# tracker1.net
KiCad netlist of a schematic drawn in EAGLE
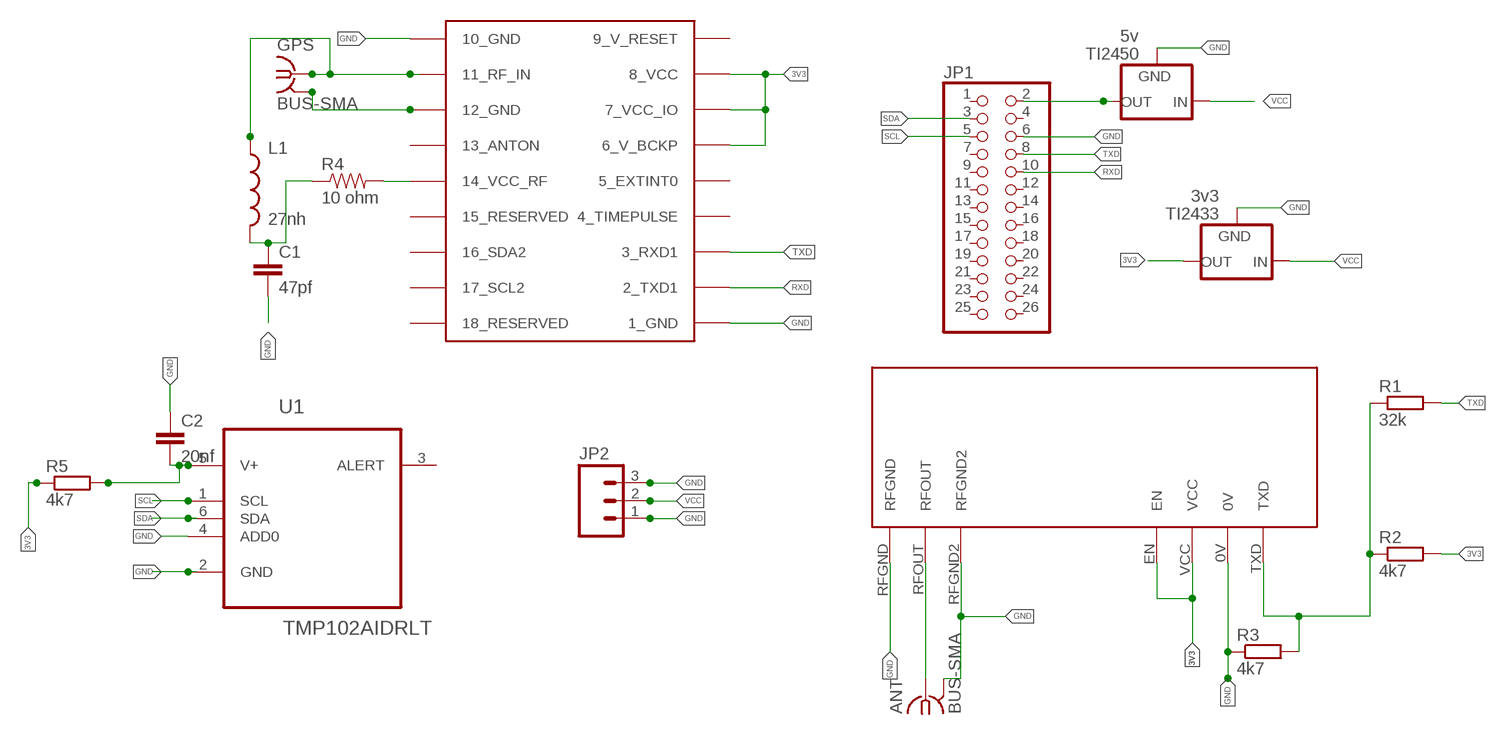
[diagram p0: schematic, sheet 1]

(export (version "E")
  (design (tool "Eeschema 10.0.6"))
  (components
    (comp (ref "ANT")
      (value "BUS-SMA")
      (footprint "eagle-import:BUS-SMA")
      (libsource (lib "eagle-import") (part "BUS-SMA"))
    )
    (comp (ref "C1")
      (value "47pf")
      (footprint "eagle-import:0603-CAP")
      (libsource (lib "eagle-import") (part "CAP0603-CAP"))
    )
    (comp (ref "C2")
      (value "20nf")
      (footprint "eagle-import:C0603")
      (libsource (lib "eagle-import") (part "C-EUC0603"))
    )
    (comp (ref "GPS")
      (value "BUS-SMA")
      (footprint "eagle-import:BUS-SMA")
      (libsource (lib "eagle-import") (part "BUS-SMA"))
    )
    (comp (ref "JP1")
      (value "PINHD-2X13")
      (footprint "eagle-import:2X13")
      (libsource (lib "eagle-import") (part "PINHD-2X13"))
    )
    (comp (ref "JP2")
      (value "M03PTH")
      (footprint "eagle-import:1X03")
      (libsource (lib "eagle-import") (part "M03PTH"))
    )
    (comp (ref "L1")
      (value "27nh")
      (footprint "eagle-import:0603")
      (libsource (lib "eagle-import") (part "INDUCTOR0603"))
    )
    (comp (ref "R1")
      (value "32k")
      (footprint "eagle-import:R0603")
      (libsource (lib "eagle-import") (part "R-EU_R0603"))
    )
    (comp (ref "R2")
      (value "4k7")
      (footprint "eagle-import:R0603")
      (libsource (lib "eagle-import") (part "R-EU_R0603"))
    )
    (comp (ref "R3")
      (value "4k7")
      (footprint "eagle-import:R0603")
      (libsource (lib "eagle-import") (part "R-EU_R0603"))
    )
    (comp (ref "R4")
      (value "10 ohm")
      (footprint "eagle-import:0603-RES")
      (libsource (lib "eagle-import") (part "RESISTOR0603"))
    )
    (comp (ref "R5")
      (value "4k7")
      (footprint "eagle-import:R0603")
      (libsource (lib "eagle-import") (part "R-EU_R0603"))
    )
    (comp (ref "TI2433")
      (value "3v3")
      (footprint "eagle-import:TO-220-ALT")
      (libsource (lib "eagle-import") (part "V_REG_78XX-TO-220"))
    )
    (comp (ref "TI2450")
      (value "5v")
      (footprint "eagle-import:TO-220-ALT")
      (libsource (lib "eagle-import") (part "V_REG_78XX-TO-220"))
    )
    (comp (ref "U$1")
      (value "NTX2")
      (footprint "eagle-import:NTX2")
      (libsource (lib "eagle-import") (part "NTX2"))
    )
    (comp (ref "U$2")
      (value "UBLOX_MAX")
      (footprint "eagle-import:UBLOX_MAX")
      (libsource (lib "eagle-import") (part "UBLOX_MAX"))
    )
    (comp (ref "U1")
      (value "TMP102AIDRLT")
      (footprint "eagle-import:SOT50P160X60-6N")
      (libsource (lib "eagle-import") (part "TMP102AIDRLT"))
    )
  )
  (nets
    (net (code "1") (name "/9_V_RESET") (class "Default")
      (node (ref "U$2") (pin "9_V_RESET") (pinfunction "9_V_RESET_9_V_RESET") (pintype "power_in"))
    )
    (net (code "2") (name "3V3") (class "Default")
      (node (ref "C2") (pin "2") (pinfunction "2_2") (pintype "passive"))
      (node (ref "R2") (pin "2") (pinfunction "2_2") (pintype "passive"))
      (node (ref "R5") (pin "1") (pinfunction "1_1") (pintype "passive"))
      (node (ref "R5") (pin "2") (pinfunction "2_2") (pintype "passive"))
      (node (ref "TI2433") (pin "OUT") (pinfunction "OUT_OUT") (pintype "output"))
      (node (ref "U$1") (pin "EN") (pinfunction "EN_EN") (pintype "bidirectional"))
      (node (ref "U$1") (pin "VCC") (pinfunction "VCC_VCC") (pintype "bidirectional"))
      (node (ref "U$2") (pin "6_V_BCKP") (pinfunction "6_V_BCKP_6_V_BCKP") (pintype "bidirectional"))
      (node (ref "U$2") (pin "7_VCC_IO") (pinfunction "7_VCC_IO_7_VCC_IO") (pintype "power_in"))
      (node (ref "U$2") (pin "8_VCC") (pinfunction "8_VCC_8_VCC") (pintype "power_in"))
      (node (ref "U1") (pin "5") (pinfunction "V+_5") (pintype "power_in"))
    )
    (net (code "3") (name "GND") (class "Default")
      (node (ref "ANT") (pin "2") (pinfunction "GND_2") (pintype "power_in"))
      (node (ref "ANT") (pin "3") (pinfunction "GND_3") (pintype "power_in"))
      (node (ref "ANT") (pin "4") (pinfunction "GND_4") (pintype "power_in"))
      (node (ref "ANT") (pin "5") (pinfunction "GND_5") (pintype "power_in"))
      (node (ref "C1") (pin "2") (pinfunction "2_2") (pintype "passive"))
      (node (ref "C2") (pin "1") (pinfunction "1_1") (pintype "passive"))
      (node (ref "GPS") (pin "2") (pinfunction "GND_2") (pintype "power_in"))
      (node (ref "GPS") (pin "3") (pinfunction "GND_3") (pintype "power_in"))
      (node (ref "GPS") (pin "4") (pinfunction "GND_4") (pintype "power_in"))
      (node (ref "GPS") (pin "5") (pinfunction "GND_5") (pintype "power_in"))
      (node (ref "JP1") (pin "6") (pinfunction "6_6") (pintype "passive"))
      (node (ref "JP2") (pin "1") (pinfunction "1_1") (pintype "passive"))
      (node (ref "JP2") (pin "3") (pinfunction "3_3") (pintype "passive"))
      (node (ref "R3") (pin "1") (pinfunction "1_1") (pintype "passive"))
      (node (ref "TI2433") (pin "GND") (pinfunction "GND_GND") (pintype "input"))
      (node (ref "TI2450") (pin "GND") (pinfunction "GND_GND") (pintype "input"))
      (node (ref "U$1") (pin "0V") (pinfunction "0V_0V") (pintype "bidirectional"))
      (node (ref "U$1") (pin "RFGND") (pinfunction "RFGND_RFGND") (pintype "bidirectional"))
      (node (ref "U$1") (pin "RFGND2") (pinfunction "RFGND2_RFGND2") (pintype "bidirectional"))
      (node (ref "U$2") (pin "10_GND") (pinfunction "10_GND_10_GND") (pintype "power_in"))
      (node (ref "U$2") (pin "12_GND") (pinfunction "12_GND_12_GND") (pintype "power_in"))
      (node (ref "U$2") (pin "1_GND") (pinfunction "1_GND_1_GND") (pintype "power_in"))
      (node (ref "U1") (pin "2") (pinfunction "GND_2") (pintype "passive"))
      (node (ref "U1") (pin "4") (pinfunction "ADD0_4") (pintype "input"))
    )
    (net (code "4") (name "Net-(ANT-Pad1)") (class "Default")
      (node (ref "ANT") (pin "1") (pinfunction "1_1") (pintype "passive"))
      (node (ref "U$1") (pin "RFOUT") (pinfunction "RFOUT_RFOUT") (pintype "bidirectional"))
    )
    (net (code "5") (name "Net-(C1-Pad1)") (class "Default")
      (node (ref "C1") (pin "1") (pinfunction "1_1") (pintype "passive"))
      (node (ref "L1") (pin "2") (pinfunction "2_2") (pintype "passive"))
      (node (ref "R4") (pin "1") (pinfunction "1_1") (pintype "passive"))
    )
    (net (code "6") (name "Net-(GPS-Pad1)") (class "Default")
      (node (ref "GPS") (pin "1") (pinfunction "1_1") (pintype "passive"))
      (node (ref "L1") (pin "1") (pinfunction "1_1") (pintype "passive"))
      (node (ref "U$2") (pin "11_RF_IN") (pinfunction "11_RF_IN_11_RF_IN") (pintype "bidirectional"))
    )
    (net (code "7") (name "Net-(JP1-Pad2)") (class "Default")
      (node (ref "JP1") (pin "2") (pinfunction "2_2") (pintype "passive"))
      (node (ref "TI2450") (pin "OUT") (pinfunction "OUT_OUT") (pintype "output"))
    )
    (net (code "8") (name "Net-(R1-Pad1)") (class "Default")
      (node (ref "R1") (pin "1") (pinfunction "1_1") (pintype "passive"))
      (node (ref "R2") (pin "1") (pinfunction "1_1") (pintype "passive"))
      (node (ref "R3") (pin "2") (pinfunction "2_2") (pintype "passive"))
      (node (ref "U$1") (pin "TXD") (pinfunction "TXD_TXD") (pintype "bidirectional"))
    )
    (net (code "9") (name "Net-(R4-Pad2)") (class "Default")
      (node (ref "R4") (pin "2") (pinfunction "2_2") (pintype "passive"))
      (node (ref "U$2") (pin "14_VCC_RF") (pinfunction "14_VCC_RF_14_VCC_RF") (pintype "bidirectional"))
    )
    (net (code "10") (name "RXD") (class "Default")
      (node (ref "JP1") (pin "10") (pinfunction "10_10") (pintype "passive"))
      (node (ref "U$2") (pin "2_TXD1") (pinfunction "2_TXD1_2_TXD1") (pintype "bidirectional"))
    )
    (net (code "11") (name "SCL") (class "Default")
      (node (ref "JP1") (pin "5") (pinfunction "5_5") (pintype "passive"))
      (node (ref "U1") (pin "1") (pinfunction "SCL_1") (pintype "bidirectional"))
    )
    (net (code "12") (name "SDA") (class "Default")
      (node (ref "JP1") (pin "3") (pinfunction "3_3") (pintype "passive"))
      (node (ref "U1") (pin "6") (pinfunction "SDA_6") (pintype "bidirectional"))
    )
    (net (code "13") (name "TXD") (class "Default")
      (node (ref "JP1") (pin "8") (pinfunction "8_8") (pintype "passive"))
      (node (ref "R1") (pin "2") (pinfunction "2_2") (pintype "passive"))
      (node (ref "U$2") (pin "3_RXD1") (pinfunction "3_RXD1_3_RXD1") (pintype "bidirectional"))
    )
    (net (code "14") (name "VCC") (class "Default")
      (node (ref "JP2") (pin "2") (pinfunction "2_2") (pintype "passive"))
      (node (ref "TI2433") (pin "IN") (pinfunction "IN_IN") (pintype "input"))
      (node (ref "TI2450") (pin "IN") (pinfunction "IN_IN") (pintype "input"))
    )
    (net (code "15") (name "unconnected-(JP1-Pad1)") (class "Default")
      (node (ref "JP1") (pin "1") (pinfunction "1_1") (pintype "passive"))
    )
    (net (code "16") (name "unconnected-(JP1-Pad4)") (class "Default")
      (node (ref "JP1") (pin "4") (pinfunction "4_4") (pintype "passive"))
    )
    (net (code "17") (name "unconnected-(JP1-Pad7)") (class "Default")
      (node (ref "JP1") (pin "7") (pinfunction "7_7") (pintype "passive"))
    )
    (net (code "18") (name "unconnected-(JP1-Pad9)") (class "Default")
      (node (ref "JP1") (pin "9") (pinfunction "9_9") (pintype "passive"))
    )
    (net (code "19") (name "unconnected-(JP1-Pad11)") (class "Default")
      (node (ref "JP1") (pin "11") (pinfunction "11_11") (pintype "passive"))
    )
    (net (code "20") (name "unconnected-(JP1-Pad12)") (class "Default")
      (node (ref "JP1") (pin "12") (pinfunction "12_12") (pintype "passive"))
    )
    (net (code "21") (name "unconnected-(JP1-Pad13)") (class "Default")
      (node (ref "JP1") (pin "13") (pinfunction "13_13") (pintype "passive"))
    )
    (net (code "22") (name "unconnected-(JP1-Pad14)") (class "Default")
      (node (ref "JP1") (pin "14") (pinfunction "14_14") (pintype "passive"))
    )
    (net (code "23") (name "unconnected-(JP1-Pad15)") (class "Default")
      (node (ref "JP1") (pin "15") (pinfunction "15_15") (pintype "passive"))
    )
    (net (code "24") (name "unconnected-(JP1-Pad16)") (class "Default")
      (node (ref "JP1") (pin "16") (pinfunction "16_16") (pintype "passive"))
    )
    (net (code "25") (name "unconnected-(JP1-Pad17)") (class "Default")
      (node (ref "JP1") (pin "17") (pinfunction "17_17") (pintype "passive"))
    )
    (net (code "26") (name "unconnected-(JP1-Pad18)") (class "Default")
      (node (ref "JP1") (pin "18") (pinfunction "18_18") (pintype "passive"))
    )
    (net (code "27") (name "unconnected-(JP1-Pad19)") (class "Default")
      (node (ref "JP1") (pin "19") (pinfunction "19_19") (pintype "passive"))
    )
    (net (code "28") (name "unconnected-(JP1-Pad20)") (class "Default")
      (node (ref "JP1") (pin "20") (pinfunction "20_20") (pintype "passive"))
    )
    (net (code "29") (name "unconnected-(JP1-Pad21)") (class "Default")
      (node (ref "JP1") (pin "21") (pinfunction "21_21") (pintype "passive"))
    )
    (net (code "30") (name "unconnected-(JP1-Pad22)") (class "Default")
      (node (ref "JP1") (pin "22") (pinfunction "22_22") (pintype "passive"))
    )
    (net (code "31") (name "unconnected-(JP1-Pad23)") (class "Default")
      (node (ref "JP1") (pin "23") (pinfunction "23_23") (pintype "passive"))
    )
    (net (code "32") (name "unconnected-(JP1-Pad24)") (class "Default")
      (node (ref "JP1") (pin "24") (pinfunction "24_24") (pintype "passive"))
    )
    (net (code "33") (name "unconnected-(JP1-Pad25)") (class "Default")
      (node (ref "JP1") (pin "25") (pinfunction "25_25") (pintype "passive"))
    )
    (net (code "34") (name "unconnected-(JP1-Pad26)") (class "Default")
      (node (ref "JP1") (pin "26") (pinfunction "26_26") (pintype "passive"))
    )
    (net (code "35") (name "unconnected-(U$2-Pad4_TIMEPULSE)") (class "Default")
      (node (ref "U$2") (pin "4_TIMEPULSE") (pinfunction "4_TIMEPULSE_4_TIMEPULSE") (pintype "bidirectional"))
    )
    (net (code "36") (name "unconnected-(U$2-Pad5_EXTINT0)") (class "Default")
      (node (ref "U$2") (pin "5_EXTINT0") (pinfunction "5_EXTINT0_5_EXTINT0") (pintype "bidirectional"))
    )
    (net (code "37") (name "unconnected-(U$2-Pad13_ANTON)") (class "Default")
      (node (ref "U$2") (pin "13_ANTON") (pinfunction "13_ANTON_13_ANTON") (pintype "bidirectional"))
    )
    (net (code "38") (name "unconnected-(U$2-Pad15_RESERVED)") (class "Default")
      (node (ref "U$2") (pin "15_RESERVED") (pinfunction "15_RESERVED_15_RESERVED") (pintype "bidirectional"))
    )
    (net (code "39") (name "unconnected-(U$2-Pad16_SDA2)") (class "Default")
      (node (ref "U$2") (pin "16_SDA2") (pinfunction "16_SDA2_16_SDA2") (pintype "bidirectional"))
    )
    (net (code "40") (name "unconnected-(U$2-Pad17_SCL2)") (class "Default")
      (node (ref "U$2") (pin "17_SCL2") (pinfunction "17_SCL2_17_SCL2") (pintype "bidirectional"))
    )
    (net (code "41") (name "unconnected-(U$2-Pad18_RESERVED)") (class "Default")
      (node (ref "U$2") (pin "18_RESERVED") (pinfunction "18_RESERVED_18_RESERVED") (pintype "bidirectional"))
    )
    (net (code "42") (name "unconnected-(U1-ALERT-Pad3)") (class "Default")
      (node (ref "U1") (pin "3") (pinfunction "ALERT_3") (pintype "output"))
    )
  )
)
